# LockBox_ver2.net
KiCad netlist of a schematic drawn in EAGLE
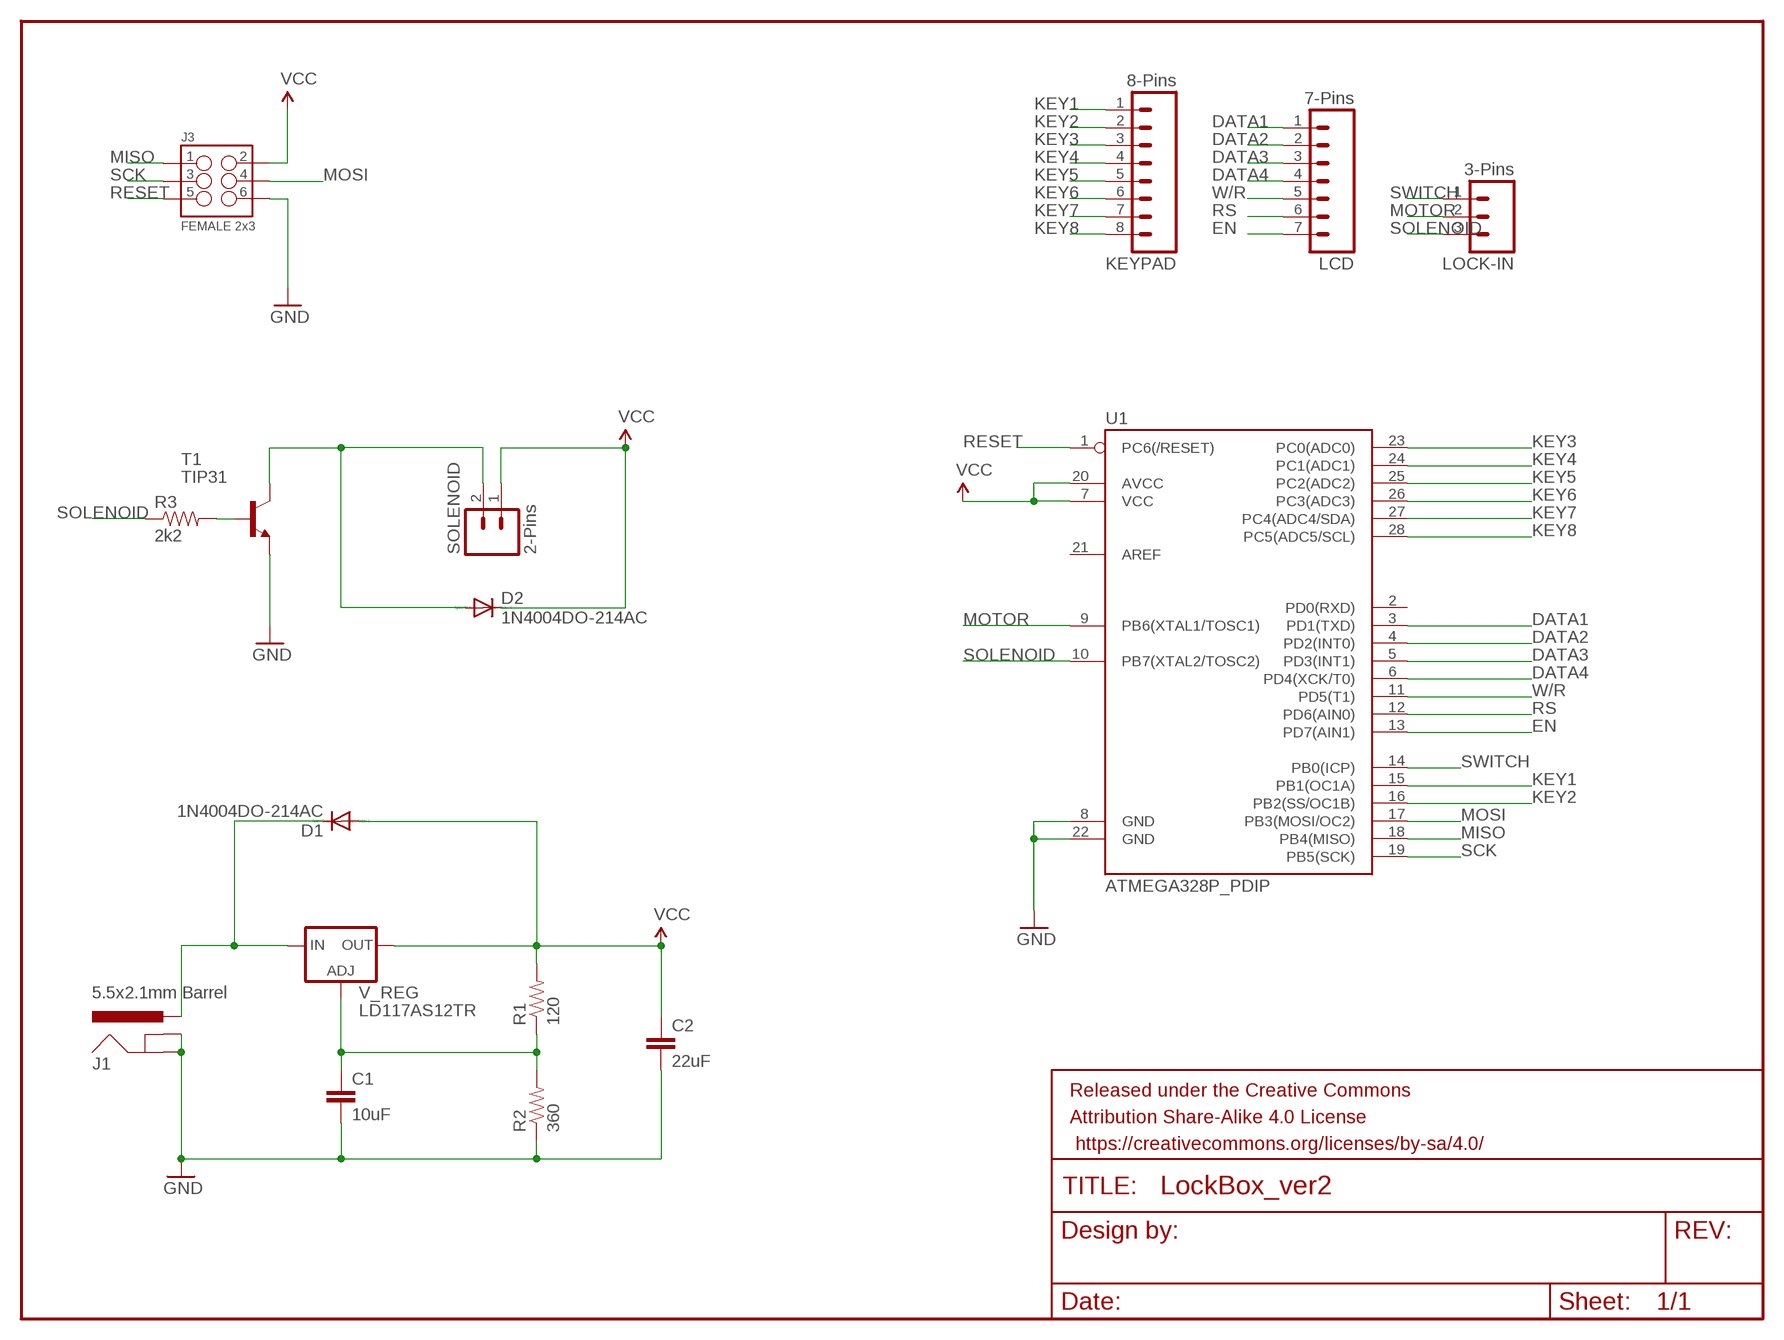
[diagram p0: schematic, sheet 1]

(export (version "E")
  (design (tool "Eeschema 10.0.6"))
  (components
    (comp (ref "C1")
      (value "10uF")
      (footprint "eagle-import:0603-CAP")
      (libsource (lib "eagle-import") (part "CAP0603-CAP"))
    )
    (comp (ref "C2")
      (value "22uF")
      (footprint "eagle-import:0603-CAP")
      (libsource (lib "eagle-import") (part "CAP0603-CAP"))
    )
    (comp (ref "D1")
      (value "1N4004DO-214AC")
      (footprint "eagle-import:DO-214AC")
      (libsource (lib "eagle-import") (part "1N4004DO-214AC"))
    )
    (comp (ref "D2")
      (value "1N4004DO-214AC")
      (footprint "eagle-import:DO-214AC")
      (libsource (lib "eagle-import") (part "1N4004DO-214AC"))
    )
    (comp (ref "FRAME1")
      (value "FRAME-LETTER")
      (footprint "eagle-import:CREATIVE_COMMONS")
      (libsource (lib "eagle-import") (part "FRAME-LETTER"))
    )
    (comp (ref "J1")
      (value "5.5x2.1mm Barrel")
      (footprint "eagle-import:POWER_JACK_SMD")
      (libsource (lib "eagle-import") (part "POWER_JACKSMD"))
    )
    (comp (ref "J3")
      (value "FEMALE 2x3")
      (footprint "eagle-import:2X3")
      (libsource (lib "eagle-import") (part "M03X2FEMALE"))
    )
    (comp (ref "KEYPAD")
      (value "8-Pins")
      (footprint "eagle-import:1X08_ROUND")
      (libsource (lib "eagle-import") (part "M08"))
    )
    (comp (ref "LCD")
      (value "7-Pins")
      (footprint "eagle-import:1X07")
      (libsource (lib "eagle-import") (part "M07"))
    )
    (comp (ref "LOCK-IN")
      (value "3-Pins")
      (footprint "eagle-import:1X03")
      (libsource (lib "eagle-import") (part "M03PTH"))
    )
    (comp (ref "R1")
      (value "120")
      (footprint "eagle-import:0603-RES")
      (libsource (lib "eagle-import") (part "RESISTOR0603"))
    )
    (comp (ref "R2")
      (value "360")
      (footprint "eagle-import:0603-RES")
      (libsource (lib "eagle-import") (part "RESISTOR0603"))
    )
    (comp (ref "R3")
      (value "2k2")
      (footprint "eagle-import:0603-RES")
      (libsource (lib "eagle-import") (part "RESISTOR0603"))
    )
    (comp (ref "SOLENOID")
      (value "2-Pins")
      (footprint "eagle-import:1X02")
      (libsource (lib "eagle-import") (part "M02PTH"))
    )
    (comp (ref "T1")
      (value "TIP31")
      (footprint "eagle-import:TO220")
      (libsource (lib "eagle-import") (part "TIP31"))
    )
    (comp (ref "U1")
      (value "ATMEGA328P_PDIP")
      (footprint "eagle-import:DIL28-3")
      (libsource (lib "eagle-import") (part "ATMEGA328P_PDIP"))
    )
    (comp (ref "V_REG")
      (value "LD117AS12TR")
      (footprint "eagle-import:SOT223")
      (libsource (lib "eagle-import") (part "LD117A?S12TR"))
    )
  )
  (nets
    (net (code "1") (name "/DATA1") (class "Default")
      (node (ref "LCD") (pin "1") (pinfunction "1_1") (pintype "passive"))
      (node (ref "U1") (pin "3") (pinfunction "PD1(TXD)_3") (pintype "bidirectional"))
    )
    (net (code "2") (name "/DATA2") (class "Default")
      (node (ref "LCD") (pin "2") (pinfunction "2_2") (pintype "passive"))
      (node (ref "U1") (pin "4") (pinfunction "PD2(INT0)_4") (pintype "bidirectional"))
    )
    (net (code "3") (name "/DATA3") (class "Default")
      (node (ref "LCD") (pin "3") (pinfunction "3_3") (pintype "passive"))
      (node (ref "U1") (pin "5") (pinfunction "PD3(INT1)_5") (pintype "bidirectional"))
    )
    (net (code "4") (name "/DATA4") (class "Default")
      (node (ref "LCD") (pin "4") (pinfunction "4_4") (pintype "passive"))
      (node (ref "U1") (pin "6") (pinfunction "PD4(XCK/T0)_6") (pintype "bidirectional"))
    )
    (net (code "5") (name "/EN") (class "Default")
      (node (ref "LCD") (pin "7") (pinfunction "7_7") (pintype "passive"))
      (node (ref "U1") (pin "13") (pinfunction "PD7(AIN1)_13") (pintype "bidirectional"))
    )
    (net (code "6") (name "/KEY1") (class "Default")
      (node (ref "KEYPAD") (pin "1") (pinfunction "1_1") (pintype "passive"))
      (node (ref "U1") (pin "15") (pinfunction "PB1(OC1A)_15") (pintype "bidirectional"))
    )
    (net (code "7") (name "/KEY2") (class "Default")
      (node (ref "KEYPAD") (pin "2") (pinfunction "2_2") (pintype "passive"))
      (node (ref "U1") (pin "16") (pinfunction "PB2(SS/OC1B)_16") (pintype "bidirectional"))
    )
    (net (code "8") (name "/KEY3") (class "Default")
      (node (ref "KEYPAD") (pin "3") (pinfunction "3_3") (pintype "passive"))
      (node (ref "U1") (pin "23") (pinfunction "PC0(ADC0)_23") (pintype "bidirectional"))
    )
    (net (code "9") (name "/KEY4") (class "Default")
      (node (ref "KEYPAD") (pin "4") (pinfunction "4_4") (pintype "passive"))
      (node (ref "U1") (pin "24") (pinfunction "PC1(ADC1)_24") (pintype "bidirectional"))
    )
    (net (code "10") (name "/KEY5") (class "Default")
      (node (ref "KEYPAD") (pin "5") (pinfunction "5_5") (pintype "passive"))
      (node (ref "U1") (pin "25") (pinfunction "PC2(ADC2)_25") (pintype "bidirectional"))
    )
    (net (code "11") (name "/KEY6") (class "Default")
      (node (ref "KEYPAD") (pin "6") (pinfunction "6_6") (pintype "passive"))
      (node (ref "U1") (pin "26") (pinfunction "PC3(ADC3)_26") (pintype "bidirectional"))
    )
    (net (code "12") (name "/KEY7") (class "Default")
      (node (ref "KEYPAD") (pin "7") (pinfunction "7_7") (pintype "passive"))
      (node (ref "U1") (pin "27") (pinfunction "PC4(ADC4/SDA)_27") (pintype "bidirectional"))
    )
    (net (code "13") (name "/KEY8") (class "Default")
      (node (ref "KEYPAD") (pin "8") (pinfunction "8_8") (pintype "passive"))
      (node (ref "U1") (pin "28") (pinfunction "PC5(ADC5/SCL)_28") (pintype "bidirectional"))
    )
    (net (code "14") (name "/MISO") (class "Default")
      (node (ref "J3") (pin "1") (pinfunction "1_1") (pintype "bidirectional"))
      (node (ref "U1") (pin "18") (pinfunction "PB4(MISO)_18") (pintype "bidirectional"))
    )
    (net (code "15") (name "/MOSI") (class "Default")
      (node (ref "J3") (pin "4") (pinfunction "4_4") (pintype "bidirectional"))
      (node (ref "U1") (pin "17") (pinfunction "PB3(MOSI/OC2)_17") (pintype "bidirectional"))
    )
    (net (code "16") (name "/MOTOR") (class "Default")
      (node (ref "LOCK-IN") (pin "2") (pinfunction "2_2") (pintype "passive"))
      (node (ref "U1") (pin "9") (pinfunction "PB6(XTAL1/TOSC1)_9") (pintype "bidirectional"))
    )
    (net (code "17") (name "/RESET") (class "Default")
      (node (ref "J3") (pin "5") (pinfunction "5_5") (pintype "bidirectional"))
      (node (ref "U1") (pin "1") (pinfunction "PC6(/RESET)_1") (pintype "bidirectional"))
    )
    (net (code "18") (name "/RS") (class "Default")
      (node (ref "LCD") (pin "6") (pinfunction "6_6") (pintype "passive"))
      (node (ref "U1") (pin "12") (pinfunction "PD6(AIN0)_12") (pintype "bidirectional"))
    )
    (net (code "19") (name "/SCK") (class "Default")
      (node (ref "J3") (pin "3") (pinfunction "3_3") (pintype "bidirectional"))
      (node (ref "U1") (pin "19") (pinfunction "PB5(SCK)_19") (pintype "bidirectional"))
    )
    (net (code "20") (name "/SOLENOID") (class "Default")
      (node (ref "LOCK-IN") (pin "3") (pinfunction "3_3") (pintype "passive"))
      (node (ref "R3") (pin "1") (pinfunction "1_1") (pintype "passive"))
      (node (ref "U1") (pin "10") (pinfunction "PB7(XTAL2/TOSC2)_10") (pintype "bidirectional"))
    )
    (net (code "21") (name "/SWITCH") (class "Default")
      (node (ref "LOCK-IN") (pin "1") (pinfunction "1_1") (pintype "passive"))
      (node (ref "U1") (pin "14") (pinfunction "PB0(ICP)_14") (pintype "bidirectional"))
    )
    (net (code "22") (name "/W{slash}R") (class "Default")
      (node (ref "LCD") (pin "5") (pinfunction "5_5") (pintype "passive"))
      (node (ref "U1") (pin "11") (pinfunction "PD5(T1)_11") (pintype "bidirectional"))
    )
    (net (code "23") (name "GND") (class "Default")
      (node (ref "C1") (pin "2") (pinfunction "2_2") (pintype "passive"))
      (node (ref "C2") (pin "2") (pinfunction "2_2") (pintype "passive"))
      (node (ref "J1") (pin "GND") (pinfunction "GNDBREAK_GND") (pintype "bidirectional"))
      (node (ref "J1") (pin "P$4") (pinfunction "GND_P$4") (pintype "bidirectional"))
      (node (ref "J3") (pin "6") (pinfunction "6_6") (pintype "bidirectional"))
      (node (ref "R2") (pin "1") (pinfunction "1_1") (pintype "passive"))
      (node (ref "T1") (pin "3") (pinfunction "E_3") (pintype "passive"))
      (node (ref "U1") (pin "22") (pinfunction "GND_22") (pintype "bidirectional"))
      (node (ref "U1") (pin "8") (pinfunction "GND_8") (pintype "bidirectional"))
    )
    (net (code "24") (name "Net-(J1-PWR)") (class "Default")
      (node (ref "D1") (pin "C") (pinfunction "C_C") (pintype "passive"))
      (node (ref "J1") (pin "VIN0") (pinfunction "PWR_VIN0") (pintype "bidirectional"))
      (node (ref "V_REG") (pin "3") (pinfunction "IN_3") (pintype "input"))
    )
    (net (code "25") (name "Net-(T1-B)") (class "Default")
      (node (ref "R3") (pin "2") (pinfunction "2_2") (pintype "passive"))
      (node (ref "T1") (pin "1") (pinfunction "B_1") (pintype "passive"))
    )
    (net (code "26") (name "Net-(T1-C)") (class "Default")
      (node (ref "D2") (pin "A") (pinfunction "A_A") (pintype "passive"))
      (node (ref "SOLENOID") (pin "2") (pinfunction "2_2") (pintype "passive"))
      (node (ref "T1") (pin "2") (pinfunction "C_2") (pintype "passive"))
    )
    (net (code "27") (name "Net-(V_REG-ADJ)") (class "Default")
      (node (ref "C1") (pin "1") (pinfunction "1_1") (pintype "passive"))
      (node (ref "R1") (pin "1") (pinfunction "1_1") (pintype "passive"))
      (node (ref "R2") (pin "2") (pinfunction "2_2") (pintype "passive"))
      (node (ref "V_REG") (pin "1") (pinfunction "ADJ_1") (pintype "input"))
    )
    (net (code "28") (name "VCC") (class "Default")
      (node (ref "C2") (pin "1") (pinfunction "1_1") (pintype "passive"))
      (node (ref "D1") (pin "A") (pinfunction "A_A") (pintype "passive"))
      (node (ref "D2") (pin "C") (pinfunction "C_C") (pintype "passive"))
      (node (ref "J3") (pin "2") (pinfunction "2_2") (pintype "bidirectional"))
      (node (ref "R1") (pin "2") (pinfunction "2_2") (pintype "passive"))
      (node (ref "SOLENOID") (pin "1") (pinfunction "1_1") (pintype "passive"))
      (node (ref "U1") (pin "20") (pinfunction "AVCC_20") (pintype "bidirectional"))
      (node (ref "U1") (pin "7") (pinfunction "VCC_7") (pintype "bidirectional"))
      (node (ref "V_REG") (pin "4") (pinfunction "OUT_4") (pintype "passive"))
    )
    (net (code "29") (name "unconnected-(U1-AREF-Pad21)") (class "Default")
      (node (ref "U1") (pin "21") (pinfunction "AREF_21") (pintype "bidirectional"))
    )
    (net (code "30") (name "unconnected-(U1-PD0(RXD)-Pad2)") (class "Default")
      (node (ref "U1") (pin "2") (pinfunction "PD0(RXD)_2") (pintype "bidirectional"))
    )
  )
)
